# Qwiic_GPS_-_Titan_X1.net
KiCad netlist of a schematic drawn in EAGLE
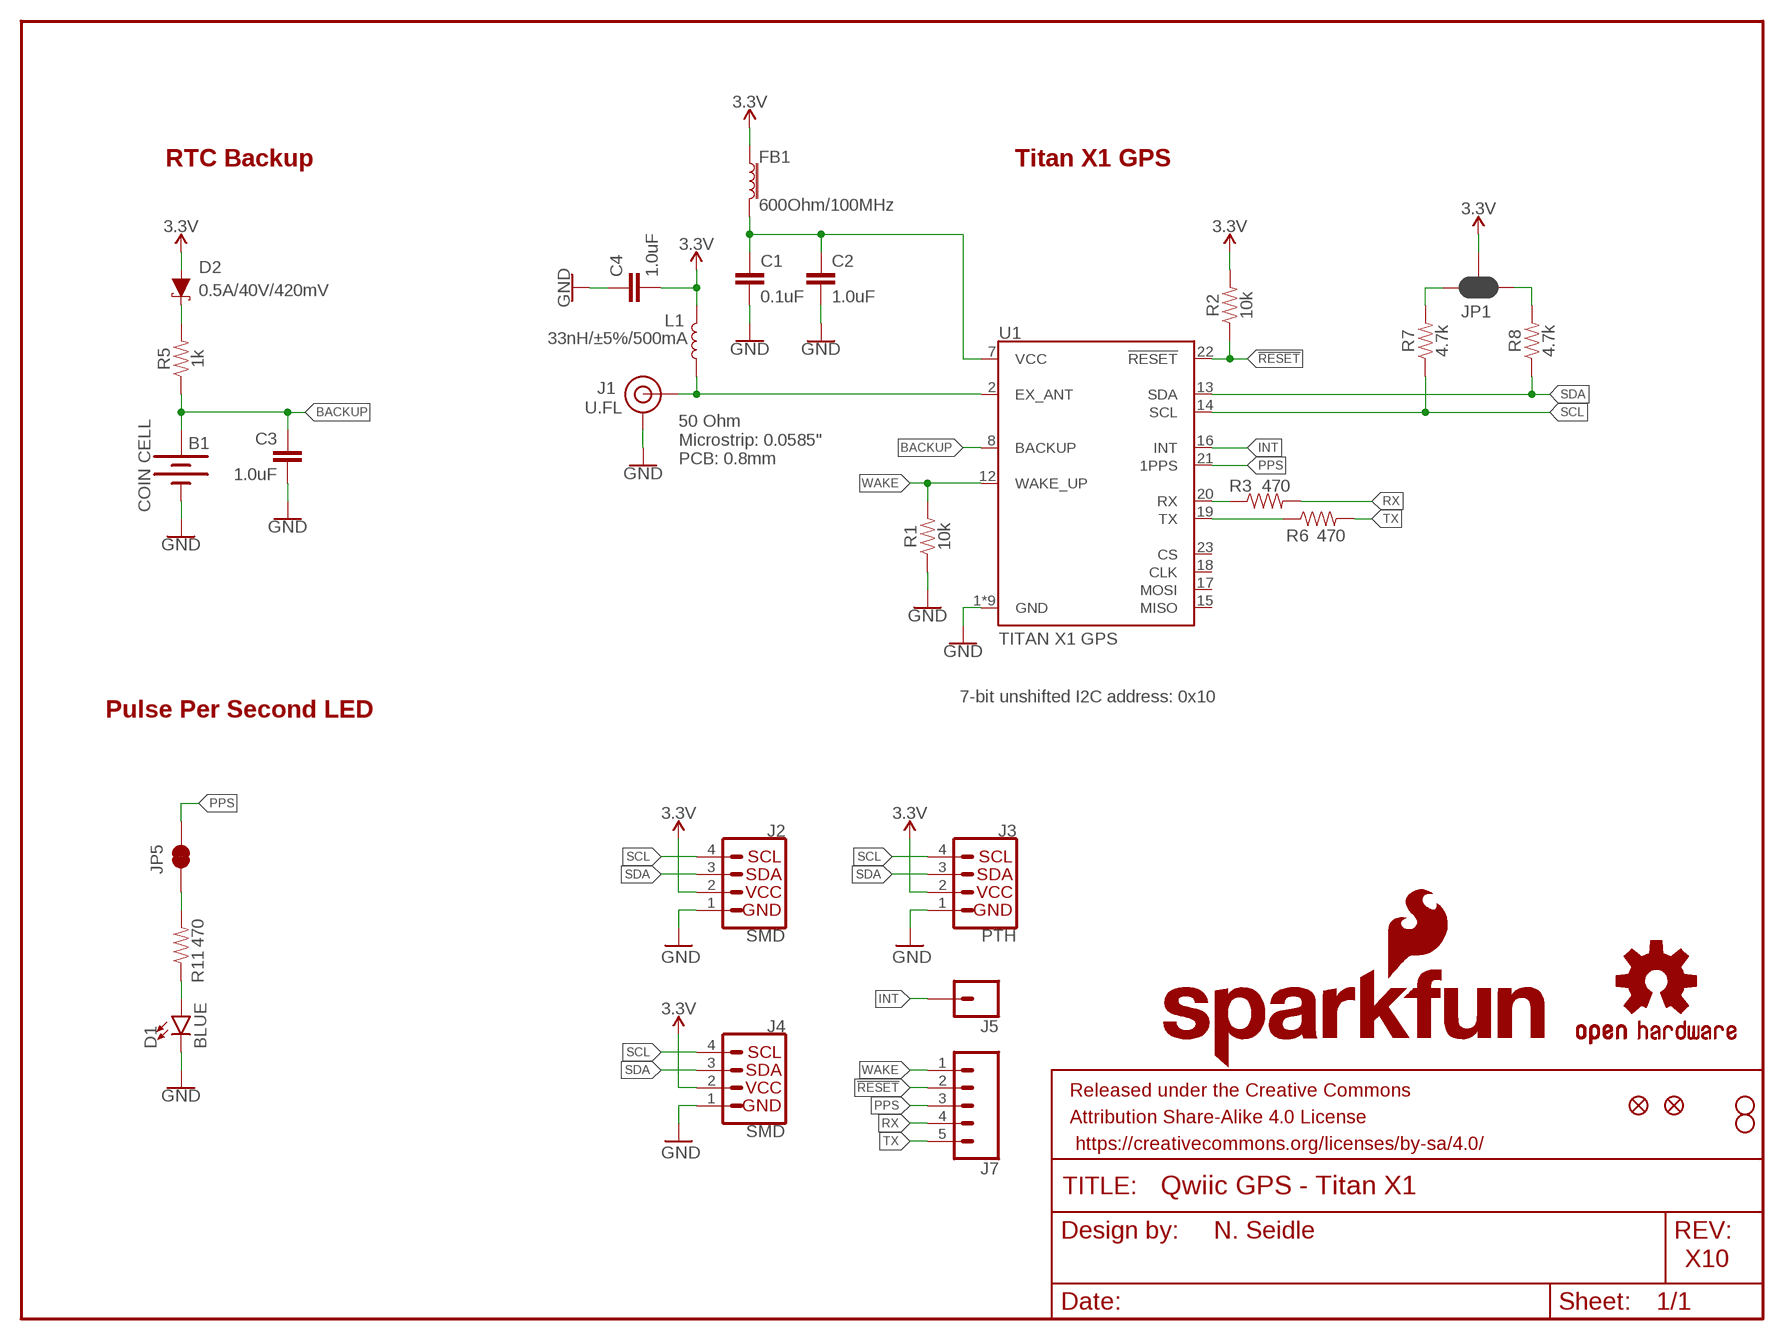
[diagram p0: schematic, sheet 1]

(export (version "E")
  (design (tool "Eeschema 10.0.6"))
  (components
    (comp (ref "B1")
      (value "COIN CELL")
      (footprint "eagle-import:6.8MM_COIN_CELL")
      (libsource (lib "eagle-import") (part "6.8MM_COIN_CELL"))
    )
    (comp (ref "C1")
      (value "0.1uF")
      (footprint "eagle-import:0603")
      (libsource (lib "eagle-import") (part "0.1UF-0603-25V-(+80/-20%)"))
    )
    (comp (ref "C2")
      (value "1.0uF")
      (footprint "eagle-import:0603")
      (libsource (lib "eagle-import") (part "1.0UF-0603-16V-10%"))
    )
    (comp (ref "C3")
      (value "1.0uF")
      (footprint "eagle-import:0603")
      (libsource (lib "eagle-import") (part "1.0UF-0603-16V-10%"))
    )
    (comp (ref "C4")
      (value "1.0uF")
      (footprint "eagle-import:0603")
      (libsource (lib "eagle-import") (part "1.0UF-0603-16V-10%"))
    )
    (comp (ref "D1")
      (value "BLUE")
      (footprint "eagle-import:LED-0603")
      (libsource (lib "eagle-import") (part "LED-BLUE0603"))
    )
    (comp (ref "D2")
      (value "0.5A/40V/420mV")
      (footprint "eagle-import:SOD-323")
      (libsource (lib "eagle-import") (part "DIODE-SCHOTTKY-PMEG4005EJ"))
    )
    (comp (ref "FB1")
      (value "600Ohm/100MHz")
      (footprint "eagle-import:0603")
      (libsource (lib "eagle-import") (part "FERRITE_BEAD-0603"))
    )
    (comp (ref "FRAME1")
      (value "FRAME-LETTER")
      (footprint "eagle-import:CREATIVE_COMMONS")
      (libsource (lib "eagle-import") (part "FRAME-LETTER"))
    )
    (comp (ref "J1")
      (value "U.FL")
      (footprint "eagle-import:U.FL")
      (libsource (lib "eagle-import") (part "U.FL"))
    )
    (comp (ref "J2")
      (value "SMD")
      (footprint "eagle-import:1X04_1MM_RA")
      (libsource (lib "eagle-import") (part "I2C_STANDARDJS-1MM"))
    )
    (comp (ref "J3")
      (value "PTH")
      (footprint "eagle-import:1X04_NO_SILK")
      (libsource (lib "eagle-import") (part "I2C_STANDARD_NO_SILK"))
    )
    (comp (ref "J4")
      (value "SMD")
      (footprint "eagle-import:1X04_1MM_RA")
      (libsource (lib "eagle-import") (part "I2C_STANDARDJS-1MM"))
    )
    (comp (ref "J5")
      (value "CONN_01PTH_NO_SILK_YES_STOP")
      (footprint "eagle-import:1X01_NO_SILK")
      (libsource (lib "eagle-import") (part "CONN_01PTH_NO_SILK_YES_STOP"))
    )
    (comp (ref "J7")
      (value "CONN_05NO_SILK")
      (footprint "eagle-import:1X05_NO_SILK")
      (libsource (lib "eagle-import") (part "CONN_05NO_SILK"))
    )
    (comp (ref "JP1")
      (value "JUMPER-SMT_3_2-NC_PASTE_SILK")
      (footprint "eagle-import:SMT-JUMPER_3_2-NC_PASTE_SILK")
      (libsource (lib "eagle-import") (part "JUMPER-SMT_3_2-NC_PASTE_SILK"))
    )
    (comp (ref "JP2")
      (value "FIDUCIALUFIDUCIAL")
      (footprint "eagle-import:MICRO-FIDUCIAL")
      (libsource (lib "eagle-import") (part "FIDUCIALUFIDUCIAL"))
    )
    (comp (ref "JP3")
      (value "STAND-OFF")
      (footprint "eagle-import:STAND-OFF")
      (libsource (lib "eagle-import") (part "STAND-OFF"))
    )
    (comp (ref "JP4")
      (value "STAND-OFF")
      (footprint "eagle-import:STAND-OFF")
      (libsource (lib "eagle-import") (part "STAND-OFF"))
    )
    (comp (ref "JP5")
      (value "JUMPER-SMT_2_NC_TRACE_NO-SILK")
      (footprint "eagle-import:SMT-JUMPER_2_NC_TRACE_NO-SILK")
      (libsource (lib "eagle-import") (part "JUMPER-SMT_2_NC_TRACE_NO-SILK"))
    )
    (comp (ref "JP6")
      (value "FIDUCIALUFIDUCIAL")
      (footprint "eagle-import:MICRO-FIDUCIAL")
      (libsource (lib "eagle-import") (part "FIDUCIALUFIDUCIAL"))
    )
    (comp (ref "L1")
      (value "33nH/±5%/500mA")
      (footprint "eagle-import:0603")
      (libsource (lib "eagle-import") (part "INDUCTOR-0603-33NH"))
    )
    (comp (ref "LOGO1")
      (value "OSHW-LOGOMINI")
      (footprint "eagle-import:OSHW-LOGO-MINI")
      (libsource (lib "eagle-import") (part "OSHW-LOGOMINI"))
    )
    (comp (ref "LOGO2")
      (value "SFE_LOGO_NAME_FLAME.1_INCH")
      (footprint "eagle-import:SFE_LOGO_NAME_FLAME_.1")
      (libsource (lib "eagle-import") (part "SFE_LOGO_NAME_FLAME.1_INCH"))
    )
    (comp (ref "R1")
      (value "10k")
      (footprint "eagle-import:0603")
      (libsource (lib "eagle-import") (part "10KOHM-0603-1/10W-1%"))
    )
    (comp (ref "R2")
      (value "10k")
      (footprint "eagle-import:0603")
      (libsource (lib "eagle-import") (part "10KOHM-0603-1/10W-1%"))
    )
    (comp (ref "R3")
      (value "470")
      (footprint "eagle-import:0603")
      (libsource (lib "eagle-import") (part "470OHM-0603-1/10W-1%"))
    )
    (comp (ref "R5")
      (value "1k")
      (footprint "eagle-import:0603")
      (libsource (lib "eagle-import") (part "1KOHM-0603-1/10W-1%"))
    )
    (comp (ref "R6")
      (value "470")
      (footprint "eagle-import:0603")
      (libsource (lib "eagle-import") (part "470OHM-0603-1/10W-1%"))
    )
    (comp (ref "R7")
      (value "4.7k")
      (footprint "eagle-import:0603")
      (libsource (lib "eagle-import") (part "4.7KOHM-0603-1/10W-1%"))
    )
    (comp (ref "R8")
      (value "4.7k")
      (footprint "eagle-import:0603")
      (libsource (lib "eagle-import") (part "4.7KOHM-0603-1/10W-1%"))
    )
    (comp (ref "R11")
      (value "470")
      (footprint "eagle-import:0603")
      (libsource (lib "eagle-import") (part "470OHM-0603-1/10W-1%"))
    )
    (comp (ref "U1")
      (value "TITAN X1 GPS")
      (footprint "eagle-import:TITAN_X1_GPS")
      (libsource (lib "eagle-import") (part "TITAN_X1_GPS"))
    )
  )
  (nets
    (net (code "1") (name "/~{RESET}") (class "Default")
      (node (ref "J7") (pin "2") (pinfunction "2_2") (pintype "passive"))
      (node (ref "R2") (pin "1") (pinfunction "1_1") (pintype "passive"))
      (node (ref "U1") (pin "22") (pinfunction "~{RESET}_22") (pintype "bidirectional"))
    )
    (net (code "2") (name "3.3V") (class "Default")
      (node (ref "C4") (pin "2") (pinfunction "2_2") (pintype "passive"))
      (node (ref "D2") (pin "A") (pinfunction "A_A") (pintype "passive"))
      (node (ref "FB1") (pin "1") (pinfunction "1_1") (pintype "passive"))
      (node (ref "J2") (pin "2") (pinfunction "VCC_2") (pintype "power_in"))
      (node (ref "J3") (pin "2") (pinfunction "VCC_2") (pintype "power_in"))
      (node (ref "J4") (pin "2") (pinfunction "VCC_2") (pintype "power_in"))
      (node (ref "JP1") (pin "2") (pinfunction "2_2") (pintype "passive"))
      (node (ref "L1") (pin "2") (pinfunction "2_2") (pintype "passive"))
      (node (ref "R2") (pin "2") (pinfunction "2_2") (pintype "passive"))
    )
    (net (code "3") (name "BACKUP") (class "Default")
      (node (ref "B1") (pin "+") (pinfunction "+_+") (pintype "power_in"))
      (node (ref "C3") (pin "1") (pinfunction "1_1") (pintype "passive"))
      (node (ref "R5") (pin "1") (pinfunction "1_1") (pintype "passive"))
      (node (ref "U1") (pin "8") (pinfunction "BACKUP_8") (pintype "bidirectional"))
    )
    (net (code "4") (name "GND") (class "Default")
      (node (ref "B1") (pin "-") (pinfunction "-_-") (pintype "power_in"))
      (node (ref "C1") (pin "2") (pinfunction "2_2") (pintype "passive"))
      (node (ref "C2") (pin "2") (pinfunction "2_2") (pintype "passive"))
      (node (ref "C3") (pin "2") (pinfunction "2_2") (pintype "passive"))
      (node (ref "C4") (pin "1") (pinfunction "1_1") (pintype "passive"))
      (node (ref "D1") (pin "C") (pinfunction "C_C") (pintype "passive"))
      (node (ref "J1") (pin "1") (pinfunction "GND_1") (pintype "bidirectional"))
      (node (ref "J1") (pin "2") (pinfunction "GND_2") (pintype "bidirectional"))
      (node (ref "J2") (pin "1") (pinfunction "GND_1") (pintype "power_in"))
      (node (ref "J3") (pin "1") (pinfunction "GND_1") (pintype "power_in"))
      (node (ref "J4") (pin "1") (pinfunction "GND_1") (pintype "power_in"))
      (node (ref "R1") (pin "1") (pinfunction "1_1") (pintype "passive"))
      (node (ref "U1") (pin "1") (pinfunction "GND_1") (pintype "bidirectional"))
      (node (ref "U1") (pin "10") (pinfunction "GND_10") (pintype "bidirectional"))
      (node (ref "U1") (pin "11") (pinfunction "GND_11") (pintype "bidirectional"))
      (node (ref "U1") (pin "24") (pinfunction "GND_24") (pintype "bidirectional"))
      (node (ref "U1") (pin "3") (pinfunction "GND_3") (pintype "bidirectional"))
      (node (ref "U1") (pin "4") (pinfunction "GND_4") (pintype "bidirectional"))
      (node (ref "U1") (pin "5") (pinfunction "GND_5") (pintype "bidirectional"))
      (node (ref "U1") (pin "6") (pinfunction "GND_6") (pintype "bidirectional"))
      (node (ref "U1") (pin "9") (pinfunction "GND_9") (pintype "bidirectional"))
    )
    (net (code "5") (name "INT") (class "Default")
      (node (ref "J5") (pin "1") (pinfunction "1_1") (pintype "passive"))
      (node (ref "U1") (pin "16") (pinfunction "INT_16") (pintype "bidirectional"))
    )
    (net (code "6") (name "Net-(D1-PadA)") (class "Default")
      (node (ref "D1") (pin "A") (pinfunction "A_A") (pintype "passive"))
      (node (ref "R11") (pin "1") (pinfunction "1_1") (pintype "passive"))
    )
    (net (code "7") (name "Net-(D2-PadC)") (class "Default")
      (node (ref "D2") (pin "C") (pinfunction "C_C") (pintype "passive"))
      (node (ref "R5") (pin "2") (pinfunction "2_2") (pintype "passive"))
    )
    (net (code "8") (name "Net-(J1-SIGNAL)") (class "Default")
      (node (ref "J1") (pin "FEED") (pinfunction "SIGNAL_FEED") (pintype "bidirectional"))
      (node (ref "L1") (pin "1") (pinfunction "1_1") (pintype "passive"))
      (node (ref "U1") (pin "2") (pinfunction "EX_ANT_2") (pintype "bidirectional"))
    )
    (net (code "9") (name "Net-(JP1-Pad1)") (class "Default")
      (node (ref "JP1") (pin "1") (pinfunction "1_1") (pintype "passive"))
      (node (ref "R8") (pin "2") (pinfunction "2_2") (pintype "passive"))
    )
    (net (code "10") (name "Net-(JP1-Pad3)") (class "Default")
      (node (ref "JP1") (pin "3") (pinfunction "3_3") (pintype "passive"))
      (node (ref "R7") (pin "2") (pinfunction "2_2") (pintype "passive"))
    )
    (net (code "11") (name "Net-(JP5-Pad1)") (class "Default")
      (node (ref "JP5") (pin "1") (pinfunction "1_1") (pintype "passive"))
      (node (ref "R11") (pin "2") (pinfunction "2_2") (pintype "passive"))
    )
    (net (code "12") (name "Net-(U1-RX)") (class "Default")
      (node (ref "R3") (pin "1") (pinfunction "1_1") (pintype "passive"))
      (node (ref "U1") (pin "20") (pinfunction "RX_20") (pintype "bidirectional"))
    )
    (net (code "13") (name "Net-(U1-TX)") (class "Default")
      (node (ref "R6") (pin "1") (pinfunction "1_1") (pintype "passive"))
      (node (ref "U1") (pin "19") (pinfunction "TX_19") (pintype "bidirectional"))
    )
    (net (code "14") (name "Net-(U1-VCC)") (class "Default")
      (node (ref "C1") (pin "1") (pinfunction "1_1") (pintype "passive"))
      (node (ref "C2") (pin "1") (pinfunction "1_1") (pintype "passive"))
      (node (ref "FB1") (pin "2") (pinfunction "2_2") (pintype "passive"))
      (node (ref "U1") (pin "7") (pinfunction "VCC_7") (pintype "bidirectional"))
    )
    (net (code "15") (name "PPS") (class "Default")
      (node (ref "J7") (pin "3") (pinfunction "3_3") (pintype "passive"))
      (node (ref "JP5") (pin "2") (pinfunction "2_2") (pintype "passive"))
      (node (ref "U1") (pin "21") (pinfunction "1PPS_21") (pintype "bidirectional"))
    )
    (net (code "16") (name "RX") (class "Default")
      (node (ref "J7") (pin "4") (pinfunction "4_4") (pintype "passive"))
      (node (ref "R3") (pin "2") (pinfunction "2_2") (pintype "passive"))
    )
    (net (code "17") (name "SCL") (class "Default")
      (node (ref "J2") (pin "4") (pinfunction "SCL_4") (pintype "passive"))
      (node (ref "J3") (pin "4") (pinfunction "SCL_4") (pintype "passive"))
      (node (ref "J4") (pin "4") (pinfunction "SCL_4") (pintype "passive"))
      (node (ref "R7") (pin "1") (pinfunction "1_1") (pintype "passive"))
      (node (ref "U1") (pin "14") (pinfunction "SCL_14") (pintype "bidirectional"))
    )
    (net (code "18") (name "SDA") (class "Default")
      (node (ref "J2") (pin "3") (pinfunction "SDA_3") (pintype "passive"))
      (node (ref "J3") (pin "3") (pinfunction "SDA_3") (pintype "passive"))
      (node (ref "J4") (pin "3") (pinfunction "SDA_3") (pintype "passive"))
      (node (ref "R8") (pin "1") (pinfunction "1_1") (pintype "passive"))
      (node (ref "U1") (pin "13") (pinfunction "SDA_13") (pintype "bidirectional"))
    )
    (net (code "19") (name "TX") (class "Default")
      (node (ref "J7") (pin "5") (pinfunction "5_5") (pintype "passive"))
      (node (ref "R6") (pin "2") (pinfunction "2_2") (pintype "passive"))
    )
    (net (code "20") (name "WAKE") (class "Default")
      (node (ref "J7") (pin "1") (pinfunction "1_1") (pintype "passive"))
      (node (ref "R1") (pin "2") (pinfunction "2_2") (pintype "passive"))
      (node (ref "U1") (pin "12") (pinfunction "WAKE_UP_12") (pintype "bidirectional"))
    )
    (net (code "21") (name "unconnected-(U1-CLK-Pad18)") (class "Default")
      (node (ref "U1") (pin "18") (pinfunction "CLK_18") (pintype "bidirectional"))
    )
    (net (code "22") (name "unconnected-(U1-CS-Pad23)") (class "Default")
      (node (ref "U1") (pin "23") (pinfunction "CS_23") (pintype "bidirectional"))
    )
    (net (code "23") (name "unconnected-(U1-MISO-Pad15)") (class "Default")
      (node (ref "U1") (pin "15") (pinfunction "MISO_15") (pintype "bidirectional"))
    )
    (net (code "24") (name "unconnected-(U1-MOSI-Pad17)") (class "Default")
      (node (ref "U1") (pin "17") (pinfunction "MOSI_17") (pintype "bidirectional"))
    )
  )
)
